# ESP32.net
KiCad netlist of a schematic drawn in Altium Designer
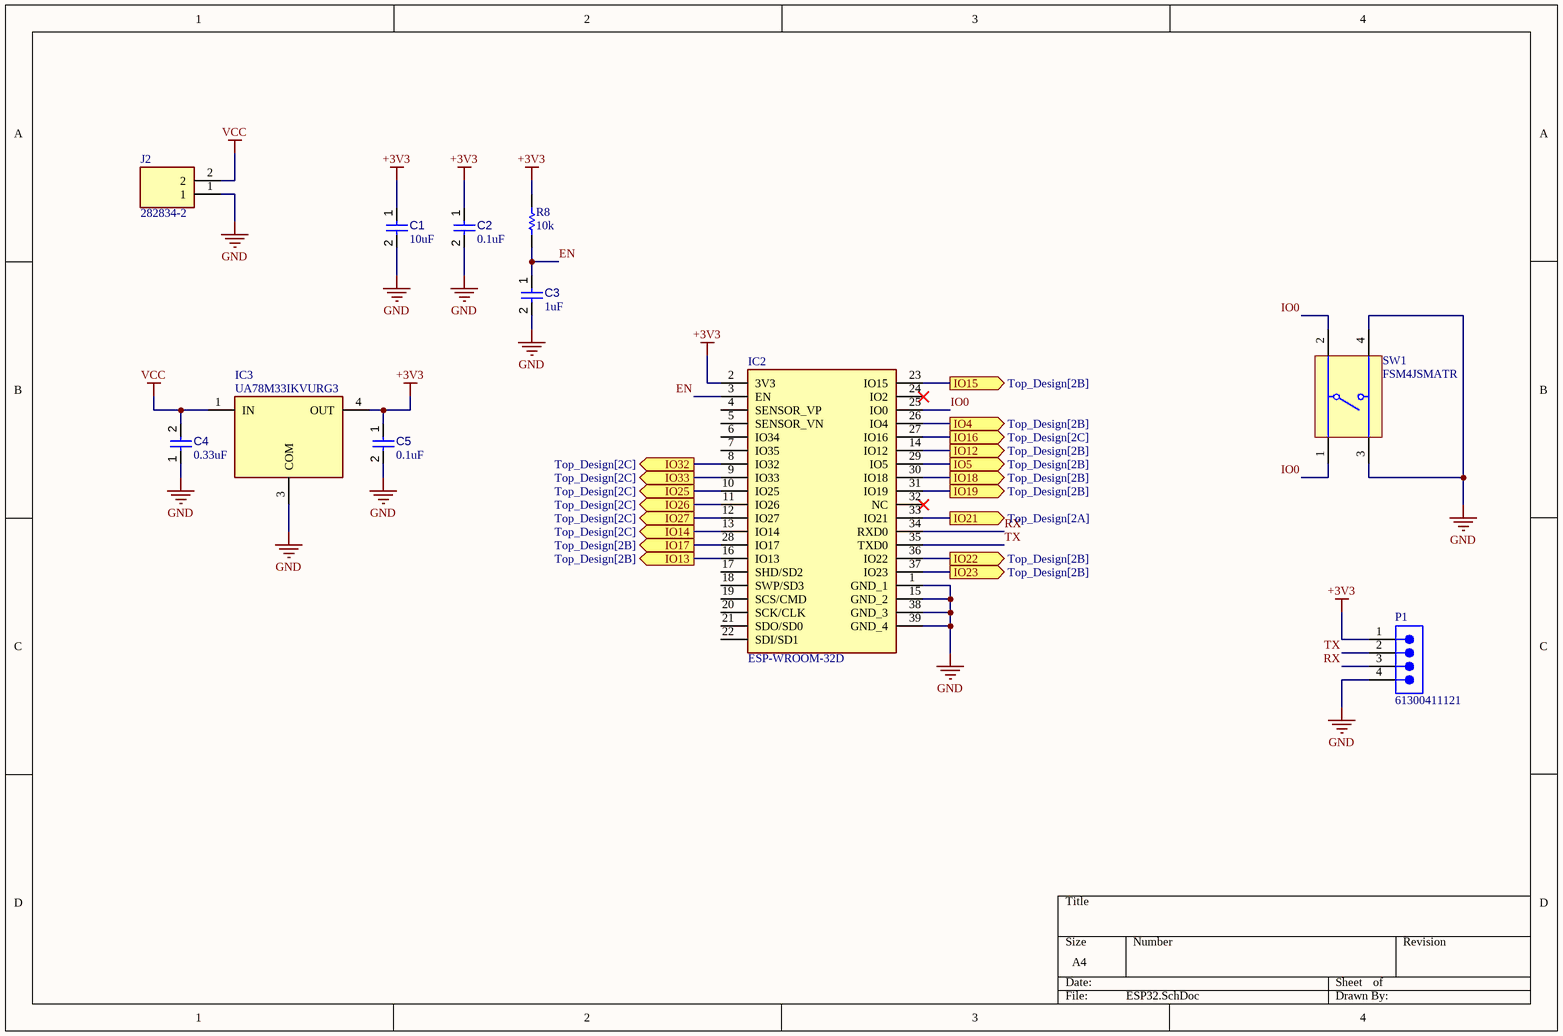
[diagram p0: ESP32.SchDoc]

(export (version "E")
  (design (tool "Eeschema 10.0.6"))
  (components
    (comp (ref "C1")
      (value "10uF")
      (footprint "CAPC2013X95X50LL10T25")
      (description "Chip Capacitor, 10 µF, +/- 10%, 50 V, 0805 (2012 Metric)")
      (fields (field (name "TOLERANCE") "10%") (field (name "Comment") "Capacitor 10 µF +/-10% 50 V 0805"))
      (libsource (lib "Arne Van der Stede") (part "CAP-NP-2"))
    )
    (comp (ref "C2")
      (value "0.1uF")
      (footprint "CAPC2013X95X50LL10T25")
      (description "Chip Capacitor, 100 nF, +/- 10%, 50 V, 0805 (2012 Metric)")
      (fields (field (name "TOLERANCE") "10%") (field (name "Comment") "Capacitor 0.1 µF +/-10% 50 V 0805"))
      (libsource (lib "Arne Van der Stede") (part "CAP-NP-2"))
    )
    (comp (ref "C3")
      (value "1uF")
      (footprint "CAPC2013X95X50LL10T25")
      (description "Chip Capacitor, 1 µF, +/- 10%, 50 V, 0805 (2012 Metric)")
      (fields (field (name "TOLERANCE") "10%") (field (name "Comment") "Capacitor 100 nF +/-10% 50 V 0805"))
      (libsource (lib "Arne Van der Stede") (part "CAP-NP-2"))
    )
    (comp (ref "C4")
      (value "0.33uF")
      (footprint "CAPC2013X95X50LL10T25")
      (description "Chip Capacitor, 0.33 µF, +/- 10%, 50 V, 0805 (2012 Metric)")
      (fields (field (name "TOLERANCE") "10%") (field (name "Comment") "Capacitor 100 nF +/-10% 50 V 0805"))
      (libsource (lib "Arne Van der Stede") (part "CAP-NP-2"))
    )
    (comp (ref "C5")
      (value "0.1uF")
      (footprint "CAPC2013X95X50LL10T25")
      (description "Chip Capacitor, 100 nF, +/- 10%, 50 V, 0805 (2012 Metric)")
      (fields (field (name "TOLERANCE") "10%") (field (name "Comment") "Capacitor 100 nF +/-10% 50 V 0805"))
      (libsource (lib "Arne Van der Stede") (part "CAP-NP-2"))
    )
    (comp (ref "IC2")
      (value "ESP-WROOM-32D")
      (footprint "SamacSys:ESPWROOM32D")
      (description "Integrated Circuit")
      (fields (field (name "MOUSER PART NUMBER") "356-ESP-WROOM-32D"))
      (libsource (lib "SamacSys") (part "ESP-WROOM-32D"))
    )
    (comp (ref "IC3")
      (value "UA78M33IKVURG3")
      (footprint "SamacSys:UA78M33IKVURG3")
      (description "Integrated Circuit")
      (fields (field (name "MOUSER PART NUMBER") "595-UA78M33IKVURG3"))
      (libsource (lib "SamacSys") (part "UA78M33IKVURG3"))
    )
    (comp (ref "J2")
      (value "282834-2")
      (footprint "SamacSys:282834-2_1")
      (description "Connector")
      (fields (field (name "MOUSER PART NUMBER") "571-282834-2"))
      (libsource (lib "*") (part "282834-2"))
    )
    (comp (ref "P1")
      (value "61300411121")
      (footprint "61300411121")
      (libsource (lib "Altium Content Vault") (part "Header_Male_1R_04P"))
    )
    (comp (ref "R8")
      (value "10k")
      (footprint "RESC2013X70X40ML20T20")
      (description "Chip Resistor, 10 KOhm, +/- 1%, 0.125 W, -55 to 155 degC, 0805 (2013 Metric)")
      (fields (field (name "TOLERANCE") "1%") (field (name "POWER") "125mW"))
      (libsource (lib "Arne Van der Stede") (part "RES-2"))
    )
    (comp (ref "SW1")
      (value "FSM4JSMATR")
      (footprint "TECO-FSM4JSMATR_V")
      (description "Micro Miniature Push Button Switch FSM JSM, 50 mA, -35 to 85 degC, 4-Pin SMD, RoHS, Tape and Reel")
      (fields (field (name "MANUFACTURER") "TE Connectivity"))
      (libsource (lib "Altium Content Vault") (part "SW-SPST-4_A"))
    )
  )
  (nets
    (net (code "1") (name "+3V3") (class "Default")
      (node (ref "C1") (pin "1") (pinfunction "1_1") (pintype "passive"))
      (node (ref "C2") (pin "1") (pinfunction "1_1") (pintype "passive"))
      (node (ref "C5") (pin "1") (pinfunction "1_1") (pintype "passive"))
      (node (ref "IC2") (pin "2") (pinfunction "3V3_2") (pintype "passive"))
      (node (ref "IC3") (pin "4") (pinfunction "OUT_4") (pintype "passive"))
      (node (ref "P1") (pin "1") (pinfunction "1_1") (pintype "passive"))
      (node (ref "R8") (pin "2") (pinfunction "2_2") (pintype "passive"))
    )
    (net (code "2") (name "/EN") (class "Default")
      (node (ref "C3") (pin "1") (pinfunction "1_1") (pintype "passive"))
      (node (ref "IC2") (pin "3") (pinfunction "EN_3") (pintype "passive"))
      (node (ref "R8") (pin "1") (pinfunction "1_1") (pintype "passive"))
    )
    (net (code "3") (name "/IO0") (class "Default")
      (node (ref "IC2") (pin "25") (pinfunction "IO0_25") (pintype "passive"))
      (node (ref "SW1") (pin "1") (pinfunction "1_1") (pintype "passive"))
      (node (ref "SW1") (pin "2") (pinfunction "2_2") (pintype "passive"))
    )
    (net (code "4") (name "/IO4") (class "Default")
      (node (ref "IC2") (pin "26") (pinfunction "IO4_26") (pintype "passive"))
    )
    (net (code "5") (name "/IO5") (class "Default")
      (node (ref "IC2") (pin "29") (pinfunction "IO5_29") (pintype "passive"))
    )
    (net (code "6") (name "/IO12") (class "Default")
      (node (ref "IC2") (pin "14") (pinfunction "IO12_14") (pintype "passive"))
    )
    (net (code "7") (name "/IO13") (class "Default")
      (node (ref "IC2") (pin "16") (pinfunction "IO13_16") (pintype "passive"))
    )
    (net (code "8") (name "/IO14") (class "Default")
      (node (ref "IC2") (pin "13") (pinfunction "IO14_13") (pintype "passive"))
    )
    (net (code "9") (name "/IO15") (class "Default")
      (node (ref "IC2") (pin "23") (pinfunction "IO15_23") (pintype "passive"))
    )
    (net (code "10") (name "/IO16") (class "Default")
      (node (ref "IC2") (pin "27") (pinfunction "IO16_27") (pintype "passive"))
    )
    (net (code "11") (name "/IO17") (class "Default")
      (node (ref "IC2") (pin "28") (pinfunction "IO17_28") (pintype "passive"))
    )
    (net (code "12") (name "/IO18") (class "Default")
      (node (ref "IC2") (pin "30") (pinfunction "IO18_30") (pintype "passive"))
    )
    (net (code "13") (name "/IO19") (class "Default")
      (node (ref "IC2") (pin "31") (pinfunction "IO19_31") (pintype "passive"))
    )
    (net (code "14") (name "/IO21") (class "Default")
      (node (ref "IC2") (pin "33") (pinfunction "IO21_33") (pintype "passive"))
    )
    (net (code "15") (name "/IO22") (class "Default")
      (node (ref "IC2") (pin "36") (pinfunction "IO22_36") (pintype "passive"))
    )
    (net (code "16") (name "/IO23") (class "Default")
      (node (ref "IC2") (pin "37") (pinfunction "IO23_37") (pintype "passive"))
    )
    (net (code "17") (name "/IO25") (class "Default")
      (node (ref "IC2") (pin "10") (pinfunction "IO25_10") (pintype "passive"))
    )
    (net (code "18") (name "/IO26") (class "Default")
      (node (ref "IC2") (pin "11") (pinfunction "IO26_11") (pintype "passive"))
    )
    (net (code "19") (name "/IO27") (class "Default")
      (node (ref "IC2") (pin "12") (pinfunction "IO27_12") (pintype "passive"))
    )
    (net (code "20") (name "/IO32") (class "Default")
      (node (ref "IC2") (pin "8") (pinfunction "IO32_8") (pintype "passive"))
    )
    (net (code "21") (name "/IO33") (class "Default")
      (node (ref "IC2") (pin "9") (pinfunction "IO33_9") (pintype "passive"))
    )
    (net (code "22") (name "/RX") (class "Default")
      (node (ref "IC2") (pin "34") (pinfunction "RXD0_34") (pintype "passive"))
      (node (ref "P1") (pin "3") (pinfunction "3_3") (pintype "passive"))
    )
    (net (code "23") (name "/TX") (class "Default")
      (node (ref "IC2") (pin "35") (pinfunction "TXD0_35") (pintype "passive"))
      (node (ref "P1") (pin "2") (pinfunction "2_2") (pintype "passive"))
    )
    (net (code "24") (name "GND") (class "Default")
      (node (ref "C1") (pin "2") (pinfunction "2_2") (pintype "passive"))
      (node (ref "C2") (pin "2") (pinfunction "2_2") (pintype "passive"))
      (node (ref "C3") (pin "2") (pinfunction "2_2") (pintype "passive"))
      (node (ref "C4") (pin "1") (pinfunction "1_1") (pintype "passive"))
      (node (ref "C5") (pin "2") (pinfunction "2_2") (pintype "passive"))
      (node (ref "IC2") (pin "1") (pinfunction "GND_1_1") (pintype "passive"))
      (node (ref "IC2") (pin "15") (pinfunction "GND_2_15") (pintype "passive"))
      (node (ref "IC2") (pin "38") (pinfunction "GND_3_38") (pintype "passive"))
      (node (ref "IC2") (pin "39") (pinfunction "GND_4_39") (pintype "passive"))
      (node (ref "IC3") (pin "3") (pinfunction "COM_3") (pintype "passive"))
      (node (ref "J2") (pin "1") (pinfunction "1_1") (pintype "passive"))
      (node (ref "P1") (pin "4") (pinfunction "4_4") (pintype "passive"))
      (node (ref "SW1") (pin "3") (pinfunction "3_3") (pintype "passive"))
      (node (ref "SW1") (pin "4") (pinfunction "4_4") (pintype "passive"))
    )
    (net (code "25") (name "VCC") (class "Default")
      (node (ref "C4") (pin "2") (pinfunction "2_2") (pintype "passive"))
      (node (ref "IC3") (pin "1") (pinfunction "IN_1") (pintype "passive"))
      (node (ref "J2") (pin "2") (pinfunction "2_2") (pintype "passive"))
    )
    (net (code "26") (name "unconnected-(IC2-IO2-Pad24)") (class "Default")
      (node (ref "IC2") (pin "24") (pinfunction "IO2_24") (pintype "passive+no_connect"))
    )
    (net (code "27") (name "unconnected-(IC2-IO34-Pad6)") (class "Default")
      (node (ref "IC2") (pin "6") (pinfunction "IO34_6") (pintype "passive"))
    )
    (net (code "28") (name "unconnected-(IC2-IO35-Pad7)") (class "Default")
      (node (ref "IC2") (pin "7") (pinfunction "IO35_7") (pintype "passive"))
    )
    (net (code "29") (name "unconnected-(IC2-NC-Pad32)") (class "Default")
      (node (ref "IC2") (pin "32") (pinfunction "NC_32") (pintype "passive+no_connect"))
    )
    (net (code "30") (name "unconnected-(IC2-SCK{slash}CLK-Pad20)") (class "Default")
      (node (ref "IC2") (pin "20") (pinfunction "SCK/CLK_20") (pintype "passive"))
    )
    (net (code "31") (name "unconnected-(IC2-SCS{slash}CMD-Pad19)") (class "Default")
      (node (ref "IC2") (pin "19") (pinfunction "SCS/CMD_19") (pintype "passive"))
    )
    (net (code "32") (name "unconnected-(IC2-SDI{slash}SD1-Pad22)") (class "Default")
      (node (ref "IC2") (pin "22") (pinfunction "SDI/SD1_22") (pintype "passive"))
    )
    (net (code "33") (name "unconnected-(IC2-SDO{slash}SD0-Pad21)") (class "Default")
      (node (ref "IC2") (pin "21") (pinfunction "SDO/SD0_21") (pintype "passive"))
    )
    (net (code "34") (name "unconnected-(IC2-SENSOR_VN-Pad5)") (class "Default")
      (node (ref "IC2") (pin "5") (pinfunction "SENSOR_VN_5") (pintype "passive"))
    )
    (net (code "35") (name "unconnected-(IC2-SENSOR_VP-Pad4)") (class "Default")
      (node (ref "IC2") (pin "4") (pinfunction "SENSOR_VP_4") (pintype "passive"))
    )
    (net (code "36") (name "unconnected-(IC2-SHD{slash}SD2-Pad17)") (class "Default")
      (node (ref "IC2") (pin "17") (pinfunction "SHD/SD2_17") (pintype "passive"))
    )
    (net (code "37") (name "unconnected-(IC2-SWP{slash}SD3-Pad18)") (class "Default")
      (node (ref "IC2") (pin "18") (pinfunction "SWP/SD3_18") (pintype "passive"))
    )
  )
)
